# 555-Sawtooth-VCO-alt.net
KiCad netlist of a schematic drawn in EAGLE
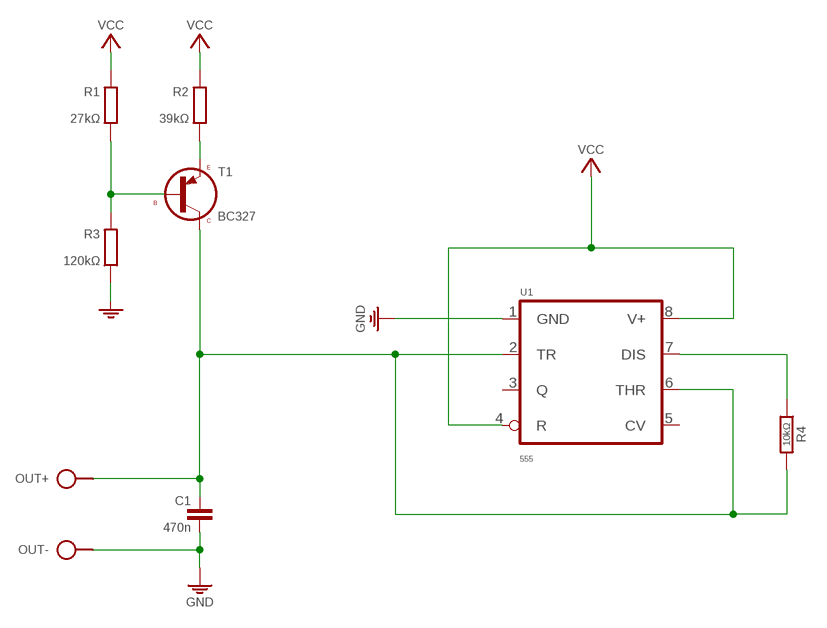
[diagram p0: schematic, sheet 1]

(export (version "E")
  (design (tool "Eeschema 10.0.6"))
  (components
    (comp (ref "C1")
      (value "470n")
      (footprint "eagle-import:C075-020X044_V")
      (libsource (lib "eagle-import") (part "C075-020X044/V"))
    )
    (comp (ref "OUT")
      (value "SPAD+--+")
      (footprint "eagle-import:SPAD-+")
      (libsource (lib "eagle-import") (part "SPAD+--+"))
    )
    (comp (ref "R1")
      (value "27kΩ")
      (footprint "eagle-import:0207_10")
      (libsource (lib "eagle-import") (part "R0207/10"))
    )
    (comp (ref "R2")
      (value "39kΩ")
      (footprint "eagle-import:0207_10")
      (libsource (lib "eagle-import") (part "R0207/10"))
    )
    (comp (ref "R3")
      (value "120kΩ")
      (footprint "eagle-import:0207_10")
      (libsource (lib "eagle-import") (part "R0207/10"))
    )
    (comp (ref "R4")
      (value "10kΩ")
      (footprint "eagle-import:0204_10")
      (libsource (lib "eagle-import") (part "R-H0204/10"))
    )
    (comp (ref "S3")
      (value "VCC_GNDPWR-R")
      (footprint "eagle-import:PWR-R")
      (libsource (lib "eagle-import") (part "VCC_GNDPWR-R"))
    )
    (comp (ref "S4")
      (value "VCC_GNDPWR-R")
      (footprint "eagle-import:PWR-R")
      (libsource (lib "eagle-import") (part "VCC_GNDPWR-R"))
    )
    (comp (ref "S5")
      (value "VCC_GNDPWR-R")
      (footprint "eagle-import:PWR-R")
      (libsource (lib "eagle-import") (part "VCC_GNDPWR-R"))
    )
    (comp (ref "T1")
      (value "BC327")
      (footprint "eagle-import:TO92")
      (libsource (lib "eagle-import") (part "BC327"))
    )
    (comp (ref "U1")
      (value "555")
      (footprint "eagle-import:DIL08")
      (libsource (lib "eagle-import") (part "555_PCB555_PCB"))
    )
  )
  (nets
    (net (code "1") (name "GND") (class "Default")
      (node (ref "C1") (pin "2") (pinfunction "2_2") (pintype "passive"))
      (node (ref "OUT") (pin "1") (pinfunction "P$1_1") (pintype "passive"))
      (node (ref "R3") (pin "2") (pinfunction "1_2") (pintype "passive"))
      (node (ref "S4") (pin "1") (pinfunction "GND_1") (pintype "power_in"))
      (node (ref "S5") (pin "1") (pinfunction "GND_1") (pintype "power_in"))
      (node (ref "U1") (pin "1") (pinfunction "GND_1") (pintype "power_in"))
    )
    (net (code "2") (name "Net-(OUTA-P$1)") (class "Default")
      (node (ref "C1") (pin "1") (pinfunction "1_1") (pintype "passive"))
      (node (ref "OUT") (pin "2") (pinfunction "P$1_2") (pintype "passive"))
      (node (ref "R4") (pin "2") (pinfunction "2_2") (pintype "passive"))
      (node (ref "T1") (pin "1") (pinfunction "C_1") (pintype "passive"))
      (node (ref "U1") (pin "2") (pinfunction "TR_2") (pintype "input"))
      (node (ref "U1") (pin "6") (pinfunction "THR_6") (pintype "input"))
    )
    (net (code "3") (name "Net-(R1-1)") (class "Default")
      (node (ref "R1") (pin "2") (pinfunction "1_2") (pintype "passive"))
      (node (ref "R3") (pin "1") (pinfunction "2_1") (pintype "passive"))
      (node (ref "T1") (pin "2") (pinfunction "B_2") (pintype "passive"))
    )
    (net (code "4") (name "Net-(R2-1)") (class "Default")
      (node (ref "R2") (pin "2") (pinfunction "1_2") (pintype "passive"))
      (node (ref "T1") (pin "3") (pinfunction "E_3") (pintype "passive"))
    )
    (net (code "5") (name "Net-(U1-DIS)") (class "Default")
      (node (ref "R4") (pin "1") (pinfunction "1_1") (pintype "passive"))
      (node (ref "U1") (pin "7") (pinfunction "DIS_7") (pintype "passive"))
    )
    (net (code "6") (name "VCC") (class "Default")
      (node (ref "R1") (pin "1") (pinfunction "2_1") (pintype "passive"))
      (node (ref "R2") (pin "1") (pinfunction "2_1") (pintype "passive"))
      (node (ref "S3") (pin "2") (pinfunction "VCC_2") (pintype "power_in"))
      (node (ref "U1") (pin "4") (pinfunction "R_4") (pintype "input"))
      (node (ref "U1") (pin "8") (pinfunction "V+_8") (pintype "power_in"))
    )
    (net (code "7") (name "unconnected-(U1-CV-Pad5)") (class "Default")
      (node (ref "U1") (pin "5") (pinfunction "CV_5") (pintype "input"))
    )
    (net (code "8") (name "unconnected-(U1-Q-Pad3)") (class "Default")
      (node (ref "U1") (pin "3") (pinfunction "Q_3") (pintype "output"))
    )
  )
)
